# voltage_regulators.net
KiCad netlist of a schematic drawn in Altium Designer
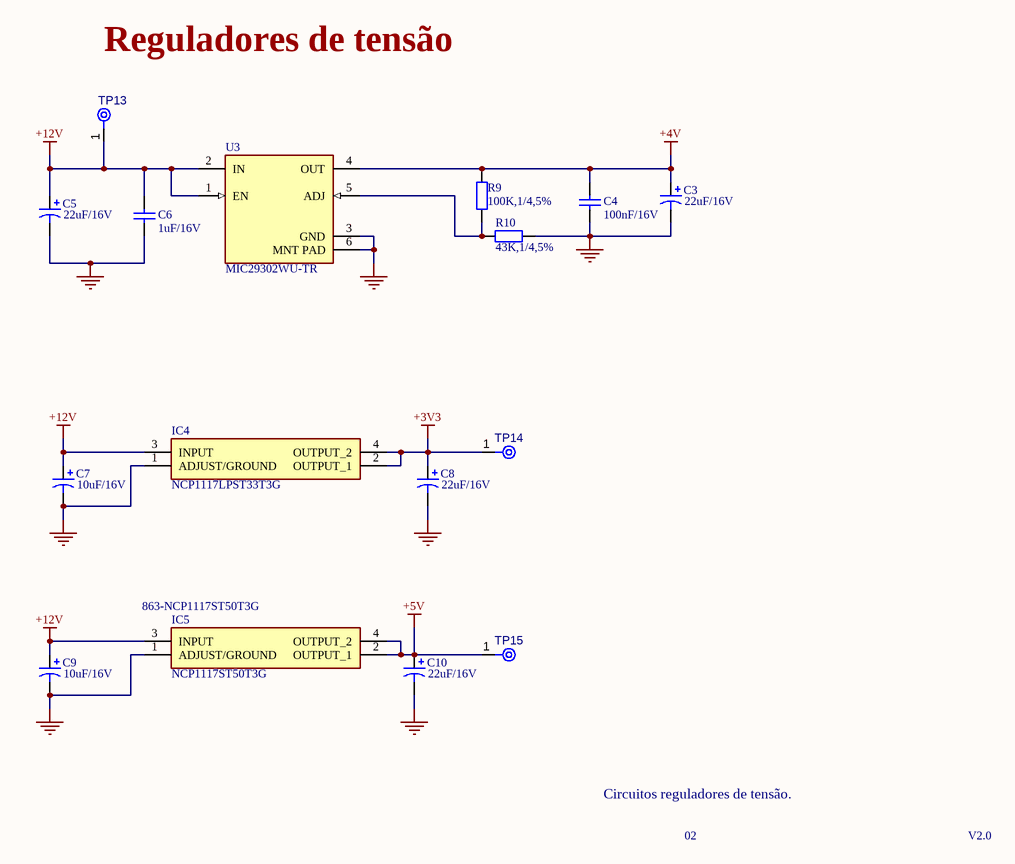
[diagram p0: voltage_regulators.SchDoc]

(export (version "E")
  (design (tool "Eeschema 10.0.6"))
  (components
    (comp (ref "C3")
      (value "22uF/16V")
      (footprint "CAPPM3216X180N")
      (description "Polarized Capacitor (Surface Mount)")
      (fields
        (field (name "MANUFACTURER") "KEMET")
        (field (name "MANUFACTURER PART NUMBER") "TF08A226M016APE200")
        (field (name "PUBLISHER") "Altium Limited")
      )
      (libsource (lib "Miscellaneous Devices") (part "Cap Pol3"))
    )
    (comp (ref "C4")
      (value "100nF/16V")
      (footprint "C1206")
      (description "Capacitor (Semiconductor SIM Model)")
      (fields
        (field (name "MANUFACTURER") "KEMET")
        (field (name "MANUFACTURER PART NUMBER") "C1206X104G4HACTU")
        (field (name "PUBLISHER") "Altium Limited")
      )
      (libsource (lib "Miscellaneous Devices") (part "Cap Semi"))
    )
    (comp (ref "C5")
      (value "22uF/16V")
      (footprint "CAPPM3216X180N")
      (description "Polarized Capacitor (Surface Mount)")
      (fields
        (field (name "MANUFACTURER") "KEMET")
        (field (name "MANUFACTURER PART NUMBER") "TF08A226M016APE200")
        (field (name "PUBLISHER") "Altium Limited")
      )
      (libsource (lib "Miscellaneous Devices") (part "Cap Pol3"))
    )
    (comp (ref "C6")
      (value "1uF/16V")
      (footprint "C1206")
      (description "CAP CER 1206 1UF 16V X7R 10%")
      (fields
        (field (name "MANUFACTURER") "KEMET")
        (field (name "MANUFACTURER PART NUMBER") "C1206C105K4REC7210")
        (field (name "PUBLISHER") "Altium Limited")
      )
      (libsource (lib "Miscellaneous Devices") (part "Cap Semi"))
    )
    (comp (ref "C7")
      (value "10uF/16V")
      (footprint "CAPPM3216X180N")
      (description "AVX - TCJA106M016R0200 - Tantalum Polymer Capacitor, 10 µF, 16 V, TCJ Series, ± 20%, A, 0.2 ohm")
      (fields
        (field (name "MANUFACTURER") "Kyocera AVX")
        (field (name "MANUFACTURER PART NUMBER") "TCJA106M016R0200")
        (field (name "PUBLISHER") "Altium Limited")
      )
      (libsource (lib "Miscellaneous Devices") (part "Cap Pol3"))
    )
    (comp (ref "C8")
      (value "22uF/16V")
      (footprint "CAPPM3216X180N")
      (description "Polarized Capacitor (Surface Mount)")
      (fields
        (field (name "MANUFACTURER") "KEMET")
        (field (name "MANUFACTURER PART NUMBER") "TF08A226M016APE200")
        (field (name "PUBLISHER") "Altium Limited")
      )
      (libsource (lib "Miscellaneous Devices") (part "Cap Pol3"))
    )
    (comp (ref "C9")
      (value "10uF/16V")
      (footprint "CAPPM3216X180N")
      (description "AVX - TCJA106M016R0200 - Tantalum Polymer Capacitor, 10 µF, 16 V, TCJ Series, ± 20%, A, 0.2 ohm")
      (fields
        (field (name "MANUFACTURER") "Kyocera AVX")
        (field (name "MANUFACTURER PART NUMBER") "TCJA106M016R0200")
        (field (name "PUBLISHER") "Altium Limited")
      )
      (libsource (lib "Miscellaneous Devices") (part "Cap Pol3"))
    )
    (comp (ref "C10")
      (value "22uF/16V")
      (footprint "CAPPM3216X180N")
      (description "Polarized Capacitor (Surface Mount)")
      (fields
        (field (name "MANUFACTURER") "KEMET")
        (field (name "MANUFACTURER PART NUMBER") "TF08A226M016APE200")
        (field (name "PUBLISHER") "Altium Limited")
      )
      (libsource (lib "Miscellaneous Devices") (part "Cap Pol3"))
    )
    (comp (ref "IC4")
      (value "NCP1117LPST33T3G")
      (footprint "sensor_pcblib:SOT230P700X180-4N")
      (fields (field (name "MANUFACTURER") "ON Semiconductor"))
      (libsource (lib "sensor_lib") (part "NCP1117ST33T3G"))
    )
    (comp (ref "IC5")
      (value "NCP1117ST50T3G")
      (footprint "sensor_pcblib:SOT230P700X180-4N")
      (fields
        (field (name "MOUSER PART NUMBER") "863-NCP1117ST50T3G")
        (field (name "MANUFACTURER") "ON Semiconductor")
        (field (name "MANUFACTURER PART NUMBER") "NCP1117ST33T3G")
        (field (name "SUPPLIER PART NUMBER 2") "863-NCP1117ST50T3G")
      )
      (libsource (lib "sensor_lib") (part "NCP1117ST50T3G"))
    )
    (comp (ref "R9")
      (value "100K,1/4,5%")
      (footprint "RESC3216X60N")
      (description "RES SMD 100K OHM 5% 1/4W 1206")
      (fields
        (field (name "MANUFACTURER") "Vishay Dale")
        (field (name "MANUFACTURER PART NUMBER") "CRCW1206100KJNEA")
        (field (name "PUBLISHER") "Altium Limited")
      )
      (libsource (lib "Miscellaneous Devices") (part "Res2"))
    )
    (comp (ref "R10")
      (value "43K,1/4,5%")
      (footprint "RESC3216X60N")
      (description "RES SMD 43K OHM 5% 1/4W 1206")
      (fields
        (field (name "MANUFACTURER") "Vishay Dale")
        (field (name "MANUFACTURER PART NUMBER") "CRCW120643K0JNEA")
        (field (name "PUBLISHER") "Altium Limited")
      )
      (libsource (lib "") (part "Res2_1"))
    )
    (comp (ref "TP13")
      (value "TPAD6R")
      (footprint "TP06R")
      (description "0.6mm round")
      (libsource (lib "PI2") (part "CMP-001-0001-4"))
    )
    (comp (ref "TP14")
      (value "TPAD6R")
      (footprint "TP06R")
      (description "0.6mm round")
      (libsource (lib "PI2") (part "CMP-001-0001-4"))
    )
    (comp (ref "TP15")
      (value "TPAD6R")
      (footprint "TP06R")
      (description "0.6mm round")
      (libsource (lib "PI2") (part "CMP-001-0001-4"))
    )
    (comp (ref "U3")
      (value "MIC29302WU-TR")
      (footprint "FP-C04-012-MFG")
      (description "IC REG LINEAR POS ADJ 3A TO263-5")
      (fields
        (field (name "MANUFACTURER") "Microchip")
        (field (name "OCTOPART") "https://octopart.com/mic29302wu-tr-microchip-66801318")
      )
      (libsource (lib "Altium Content Vault") (part "0db40f55fda0e91d0d14528974a446d"))
    )
  )
  (nets
    (net (code "1") (name "+3V3") (class "Default")
      (node (ref "C8") (pin "1") (pinfunction "1_1") (pintype "passive"))
      (node (ref "IC4") (pin "2") (pinfunction "OUTPUT_1_2") (pintype "passive"))
      (node (ref "IC4") (pin "4") (pinfunction "OUTPUT_2_4") (pintype "passive"))
      (node (ref "TP14") (pin "1") (pinfunction "TP_1") (pintype "passive"))
    )
    (net (code "2") (name "+4V") (class "Default")
      (node (ref "C3") (pin "1") (pinfunction "1_1") (pintype "passive"))
      (node (ref "C4") (pin "2") (pinfunction "2_2") (pintype "passive"))
      (node (ref "R9") (pin "2") (pinfunction "2_2") (pintype "passive"))
      (node (ref "U3") (pin "4") (pinfunction "OUT_4") (pintype "power_in"))
    )
    (net (code "3") (name "+5V") (class "Default")
      (node (ref "C10") (pin "1") (pinfunction "1_1") (pintype "passive"))
      (node (ref "IC5") (pin "2") (pinfunction "OUTPUT_1_2") (pintype "passive"))
      (node (ref "IC5") (pin "4") (pinfunction "OUTPUT_2_4") (pintype "passive"))
      (node (ref "TP15") (pin "1") (pinfunction "TP_1") (pintype "passive"))
    )
    (net (code "4") (name "+12V") (class "Default")
      (node (ref "C5") (pin "1") (pinfunction "1_1") (pintype "passive"))
      (node (ref "C6") (pin "2") (pinfunction "2_2") (pintype "passive"))
      (node (ref "C7") (pin "1") (pinfunction "1_1") (pintype "passive"))
      (node (ref "C9") (pin "1") (pinfunction "1_1") (pintype "passive"))
      (node (ref "IC4") (pin "3") (pinfunction "INPUT_3") (pintype "passive"))
      (node (ref "IC5") (pin "3") (pinfunction "INPUT_3") (pintype "passive"))
      (node (ref "TP13") (pin "1") (pinfunction "TP_1") (pintype "passive"))
      (node (ref "U3") (pin "1") (pinfunction "EN_1") (pintype "input"))
      (node (ref "U3") (pin "2") (pinfunction "IN_2") (pintype "power_in"))
    )
    (net (code "5") (name "GND") (class "Default")
      (node (ref "C10") (pin "2") (pinfunction "2_2") (pintype "passive"))
      (node (ref "C3") (pin "2") (pinfunction "2_2") (pintype "passive"))
      (node (ref "C4") (pin "1") (pinfunction "1_1") (pintype "passive"))
      (node (ref "C5") (pin "2") (pinfunction "2_2") (pintype "passive"))
      (node (ref "C6") (pin "1") (pinfunction "1_1") (pintype "passive"))
      (node (ref "C7") (pin "2") (pinfunction "2_2") (pintype "passive"))
      (node (ref "C8") (pin "2") (pinfunction "2_2") (pintype "passive"))
      (node (ref "C9") (pin "2") (pinfunction "2_2") (pintype "passive"))
      (node (ref "IC4") (pin "1") (pinfunction "ADJUST/GROUND_1") (pintype "passive"))
      (node (ref "IC5") (pin "1") (pinfunction "ADJUST/GROUND_1") (pintype "passive"))
      (node (ref "R10") (pin "1") (pinfunction "1_1") (pintype "passive"))
      (node (ref "U3") (pin "3") (pinfunction "GND_3") (pintype "power_in"))
      (node (ref "U3") (pin "6") (pinfunction "MNT_PAD_6") (pintype "passive"))
    )
    (net (code "6") (name "Net-(U3-ADJ)") (class "Default")
      (node (ref "R10") (pin "2") (pinfunction "2_2") (pintype "passive"))
      (node (ref "R9") (pin "1") (pinfunction "1_1") (pintype "passive"))
      (node (ref "U3") (pin "5") (pinfunction "ADJ_5") (pintype "input"))
    )
  )
)
